# Remote.net
KiCad netlist of a schematic drawn in EAGLE
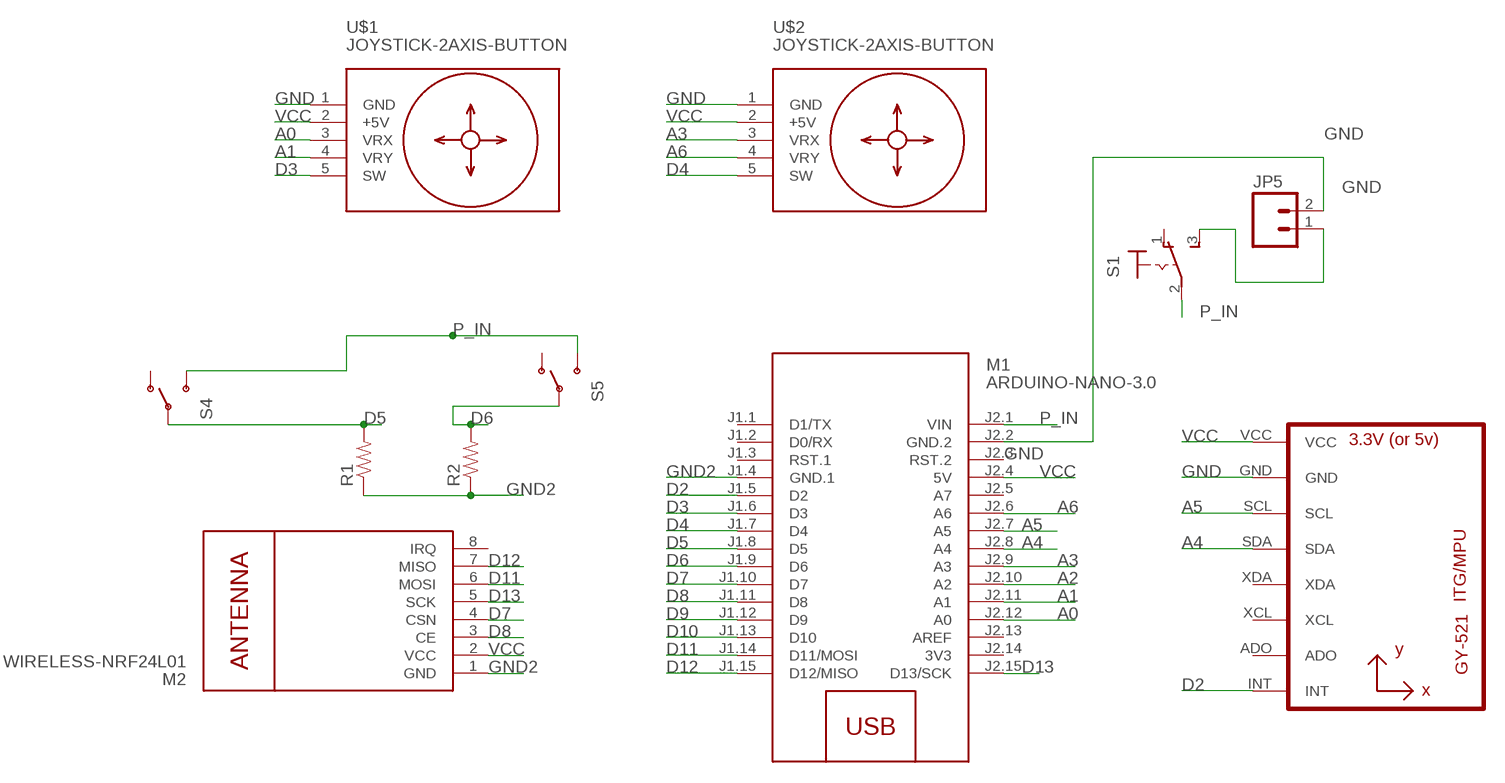
[diagram p0: schematic, sheet 1]

(export (version "E")
  (design (tool "Eeschema 10.0.6"))
  (components
    (comp (ref "JP5")
      (value "M02PTH")
      (footprint "eagle-import:1X02")
      (libsource (lib "eagle-import") (part "M02PTH"))
    )
    (comp (ref "M1")
      (value "ARDUINO-NANO-3.0")
      (footprint "eagle-import:ARDUINO-NANO-3.0")
      (libsource (lib "eagle-import") (part "ARDUINO-NANO-3.0"))
    )
    (comp (ref "M2")
      (value "WIRELESS-NRF24L01")
      (footprint "eagle-import:WIRELESS-NRF24L01")
      (libsource (lib "eagle-import") (part "WIRELESS-NRF24L01"))
    )
    (comp (ref "R1")
      (value "RESISTORAXIAL-0.3")
      (footprint "eagle-import:AXIAL-0.3")
      (libsource (lib "eagle-import") (part "RESISTORAXIAL-0.3"))
    )
    (comp (ref "R2")
      (value "RESISTORAXIAL-0.3")
      (footprint "eagle-import:AXIAL-0.3")
      (libsource (lib "eagle-import") (part "RESISTORAXIAL-0.3"))
    )
    (comp (ref "S1")
      (value "M9040P")
      (footprint "eagle-import:M9040P")
      (libsource (lib "eagle-import") (part "M9040P"))
    )
    (comp (ref "S4")
      (value "SWITCH-SPSTPTH")
      (footprint "eagle-import:SWITCH-SPDT")
      (libsource (lib "eagle-import") (part "SWITCH-SPSTPTH"))
    )
    (comp (ref "S5")
      (value "SWITCH-SPSTPTH")
      (footprint "eagle-import:SWITCH-SPDT")
      (libsource (lib "eagle-import") (part "SWITCH-SPSTPTH"))
    )
    (comp (ref "U$1")
      (value "JOYSTICK-2AXIS-BUTTON")
      (footprint "eagle-import:JOYSTICK-2AXIS-BUTTON")
      (libsource (lib "eagle-import") (part "JOYSTICK-2AXIS-BUTTON"))
    )
    (comp (ref "U$2")
      (value "JOYSTICK-2AXIS-BUTTON")
      (footprint "eagle-import:JOYSTICK-2AXIS-BUTTON")
      (libsource (lib "eagle-import") (part "JOYSTICK-2AXIS-BUTTON"))
    )
    (comp (ref "U1")
      (value "GY-521MPU6050")
      (footprint "eagle-import:GY-521")
      (libsource (lib "eagle-import") (part "GY-521MPU6050"))
    )
  )
  (nets
    (net (code "1") (name "/3V3") (class "Default")
      (node (ref "M1") (pin "J2.14") (pinfunction "3V3_J2.14") (pintype "power_in"))
    )
    (net (code "2") (name "/A0") (class "Default")
      (node (ref "M1") (pin "J2.12") (pinfunction "A0_J2.12") (pintype "bidirectional"))
      (node (ref "U$1") (pin "3") (pinfunction "VRX_3") (pintype "passive"))
    )
    (net (code "3") (name "/A1") (class "Default")
      (node (ref "M1") (pin "J2.11") (pinfunction "A1_J2.11") (pintype "bidirectional"))
      (node (ref "U$1") (pin "4") (pinfunction "VRY_4") (pintype "passive"))
    )
    (net (code "4") (name "/A2") (class "Default")
      (node (ref "M1") (pin "J2.10") (pinfunction "A2_J2.10") (pintype "bidirectional"))
    )
    (net (code "5") (name "/A3") (class "Default")
      (node (ref "M1") (pin "J2.9") (pinfunction "A3_J2.9") (pintype "bidirectional"))
      (node (ref "U$2") (pin "3") (pinfunction "VRX_3") (pintype "passive"))
    )
    (net (code "6") (name "/A4") (class "Default")
      (node (ref "M1") (pin "J2.8") (pinfunction "A4_J2.8") (pintype "bidirectional"))
      (node (ref "U1") (pin "SDA") (pinfunction "SDA_SDA") (pintype "bidirectional"))
    )
    (net (code "7") (name "/A5") (class "Default")
      (node (ref "M1") (pin "J2.7") (pinfunction "A5_J2.7") (pintype "bidirectional"))
      (node (ref "U1") (pin "SCL") (pinfunction "SCL_SCL") (pintype "bidirectional"))
    )
    (net (code "8") (name "/A6") (class "Default")
      (node (ref "M1") (pin "J2.6") (pinfunction "A6_J2.6") (pintype "bidirectional"))
      (node (ref "U$2") (pin "4") (pinfunction "VRY_4") (pintype "passive"))
    )
    (net (code "9") (name "/D2") (class "Default")
      (node (ref "M1") (pin "J1.5") (pinfunction "D2_J1.5") (pintype "bidirectional"))
      (node (ref "U1") (pin "INT") (pinfunction "INT_INT") (pintype "bidirectional"))
    )
    (net (code "10") (name "/D3") (class "Default")
      (node (ref "M1") (pin "J1.6") (pinfunction "D3_J1.6") (pintype "bidirectional"))
      (node (ref "U$1") (pin "5") (pinfunction "SW_5") (pintype "passive"))
    )
    (net (code "11") (name "/D4") (class "Default")
      (node (ref "M1") (pin "J1.7") (pinfunction "D4_J1.7") (pintype "bidirectional"))
      (node (ref "U$2") (pin "5") (pinfunction "SW_5") (pintype "passive"))
    )
    (net (code "12") (name "/D5") (class "Default")
      (node (ref "M1") (pin "J1.8") (pinfunction "D5_J1.8") (pintype "bidirectional"))
      (node (ref "R1") (pin "P$2") (pinfunction "2_P$2") (pintype "passive"))
      (node (ref "S4") (pin "2") (pinfunction "P_2") (pintype "passive"))
    )
    (net (code "13") (name "/D6") (class "Default")
      (node (ref "M1") (pin "J1.9") (pinfunction "D6_J1.9") (pintype "bidirectional"))
      (node (ref "R2") (pin "P$2") (pinfunction "2_P$2") (pintype "passive"))
      (node (ref "S5") (pin "2") (pinfunction "P_2") (pintype "passive"))
    )
    (net (code "14") (name "/D7") (class "Default")
      (node (ref "M1") (pin "J1.10") (pinfunction "D7_J1.10") (pintype "bidirectional"))
      (node (ref "M2") (pin "4") (pinfunction "CSN_4") (pintype "bidirectional"))
    )
    (net (code "15") (name "/D8") (class "Default")
      (node (ref "M1") (pin "J1.11") (pinfunction "D8_J1.11") (pintype "bidirectional"))
      (node (ref "M2") (pin "3") (pinfunction "CE_3") (pintype "bidirectional"))
    )
    (net (code "16") (name "/D9") (class "Default")
      (node (ref "M1") (pin "J1.12") (pinfunction "D9_J1.12") (pintype "bidirectional"))
    )
    (net (code "17") (name "/D10") (class "Default")
      (node (ref "M1") (pin "J1.13") (pinfunction "D10_J1.13") (pintype "bidirectional"))
    )
    (net (code "18") (name "/D11") (class "Default")
      (node (ref "M1") (pin "J1.14") (pinfunction "D11/MOSI_J1.14") (pintype "bidirectional"))
      (node (ref "M2") (pin "6") (pinfunction "MOSI_6") (pintype "bidirectional"))
    )
    (net (code "19") (name "/D12") (class "Default")
      (node (ref "M1") (pin "J1.15") (pinfunction "D12/MISO_J1.15") (pintype "bidirectional"))
      (node (ref "M2") (pin "7") (pinfunction "MISO_7") (pintype "bidirectional"))
    )
    (net (code "20") (name "/D13") (class "Default")
      (node (ref "M1") (pin "J2.15") (pinfunction "D13/SCK_J2.15") (pintype "bidirectional"))
      (node (ref "M2") (pin "5") (pinfunction "SCK_5") (pintype "bidirectional"))
    )
    (net (code "21") (name "/GND") (class "Default")
      (node (ref "JP5") (pin "2") (pinfunction "2_2") (pintype "passive"))
      (node (ref "M1") (pin "J2.2") (pinfunction "GND.2_J2.2") (pintype "power_in"))
      (node (ref "U$1") (pin "1") (pinfunction "GND_1") (pintype "power_in"))
      (node (ref "U$2") (pin "1") (pinfunction "GND_1") (pintype "power_in"))
      (node (ref "U1") (pin "GND") (pinfunction "GND_GND") (pintype "bidirectional"))
    )
    (net (code "22") (name "/GND2") (class "Default")
      (node (ref "M1") (pin "J1.4") (pinfunction "GND.1_J1.4") (pintype "power_in"))
      (node (ref "M2") (pin "1") (pinfunction "GND_1") (pintype "power_in"))
      (node (ref "R1") (pin "P$1") (pinfunction "1_P$1") (pintype "passive"))
      (node (ref "R2") (pin "P$1") (pinfunction "1_P$1") (pintype "passive"))
    )
    (net (code "23") (name "/P_IN") (class "Default")
      (node (ref "M1") (pin "J2.1") (pinfunction "VIN_J2.1") (pintype "power_in"))
      (node (ref "S1") (pin "2") (pinfunction "P_2") (pintype "passive"))
      (node (ref "S4") (pin "3") (pinfunction "S_3") (pintype "passive"))
      (node (ref "S5") (pin "3") (pinfunction "S_3") (pintype "passive"))
    )
    (net (code "24") (name "/VCC") (class "Default")
      (node (ref "M1") (pin "J2.4") (pinfunction "5V_J2.4") (pintype "power_in"))
      (node (ref "M2") (pin "2") (pinfunction "VCC_2") (pintype "power_in"))
      (node (ref "U$1") (pin "2") (pinfunction "+5V_2") (pintype "power_in"))
      (node (ref "U$2") (pin "2") (pinfunction "+5V_2") (pintype "power_in"))
      (node (ref "U1") (pin "VCC") (pinfunction "VCC_VCC") (pintype "bidirectional"))
    )
    (net (code "25") (name "Net-(S1-S)") (class "Default")
      (node (ref "JP5") (pin "1") (pinfunction "1_1") (pintype "passive"))
      (node (ref "S1") (pin "3") (pinfunction "S_3") (pintype "passive"))
    )
    (net (code "26") (name "unconnected-(M1-A7-PadJ2.5)") (class "Default")
      (node (ref "M1") (pin "J2.5") (pinfunction "A7_J2.5") (pintype "bidirectional"))
    )
    (net (code "27") (name "unconnected-(M1-AREF-PadJ2.13)") (class "Default")
      (node (ref "M1") (pin "J2.13") (pinfunction "AREF_J2.13") (pintype "bidirectional"))
    )
    (net (code "28") (name "unconnected-(M1-D0{slash}RX-PadJ1.2)") (class "Default")
      (node (ref "M1") (pin "J1.2") (pinfunction "D0/RX_J1.2") (pintype "bidirectional"))
    )
    (net (code "29") (name "unconnected-(M1-D1{slash}TX-PadJ1.1)") (class "Default")
      (node (ref "M1") (pin "J1.1") (pinfunction "D1/TX_J1.1") (pintype "bidirectional"))
    )
    (net (code "30") (name "unconnected-(M1-RST.1-PadJ1.3)") (class "Default")
      (node (ref "M1") (pin "J1.3") (pinfunction "RST.1_J1.3") (pintype "bidirectional"))
    )
    (net (code "31") (name "unconnected-(M1-RST.2-PadJ2.3)") (class "Default")
      (node (ref "M1") (pin "J2.3") (pinfunction "RST.2_J2.3") (pintype "bidirectional"))
    )
    (net (code "32") (name "unconnected-(M2-IRQ-Pad8)") (class "Default")
      (node (ref "M2") (pin "8") (pinfunction "IRQ_8") (pintype "bidirectional"))
    )
    (net (code "33") (name "unconnected-(S1-O-Pad1)") (class "Default")
      (node (ref "S1") (pin "1") (pinfunction "O_1") (pintype "passive"))
    )
    (net (code "34") (name "unconnected-(S4-O-Pad1)") (class "Default")
      (node (ref "S4") (pin "1") (pinfunction "O_1") (pintype "passive"))
    )
    (net (code "35") (name "unconnected-(S5-O-Pad1)") (class "Default")
      (node (ref "S5") (pin "1") (pinfunction "O_1") (pintype "passive"))
    )
    (net (code "36") (name "unconnected-(U1-PadADO)") (class "Default")
      (node (ref "U1") (pin "ADO") (pinfunction "ADO_ADO") (pintype "bidirectional"))
    )
    (net (code "37") (name "unconnected-(U1-PadXCL)") (class "Default")
      (node (ref "U1") (pin "XCL") (pinfunction "XCL_XCL") (pintype "bidirectional"))
    )
    (net (code "38") (name "unconnected-(U1-PadXDA)") (class "Default")
      (node (ref "U1") (pin "XDA") (pinfunction "XDA_XDA") (pintype "bidirectional"))
    )
  )
)
